# hvreg_feedback_2PS.net
KiCad netlist of a schematic drawn in EAGLE
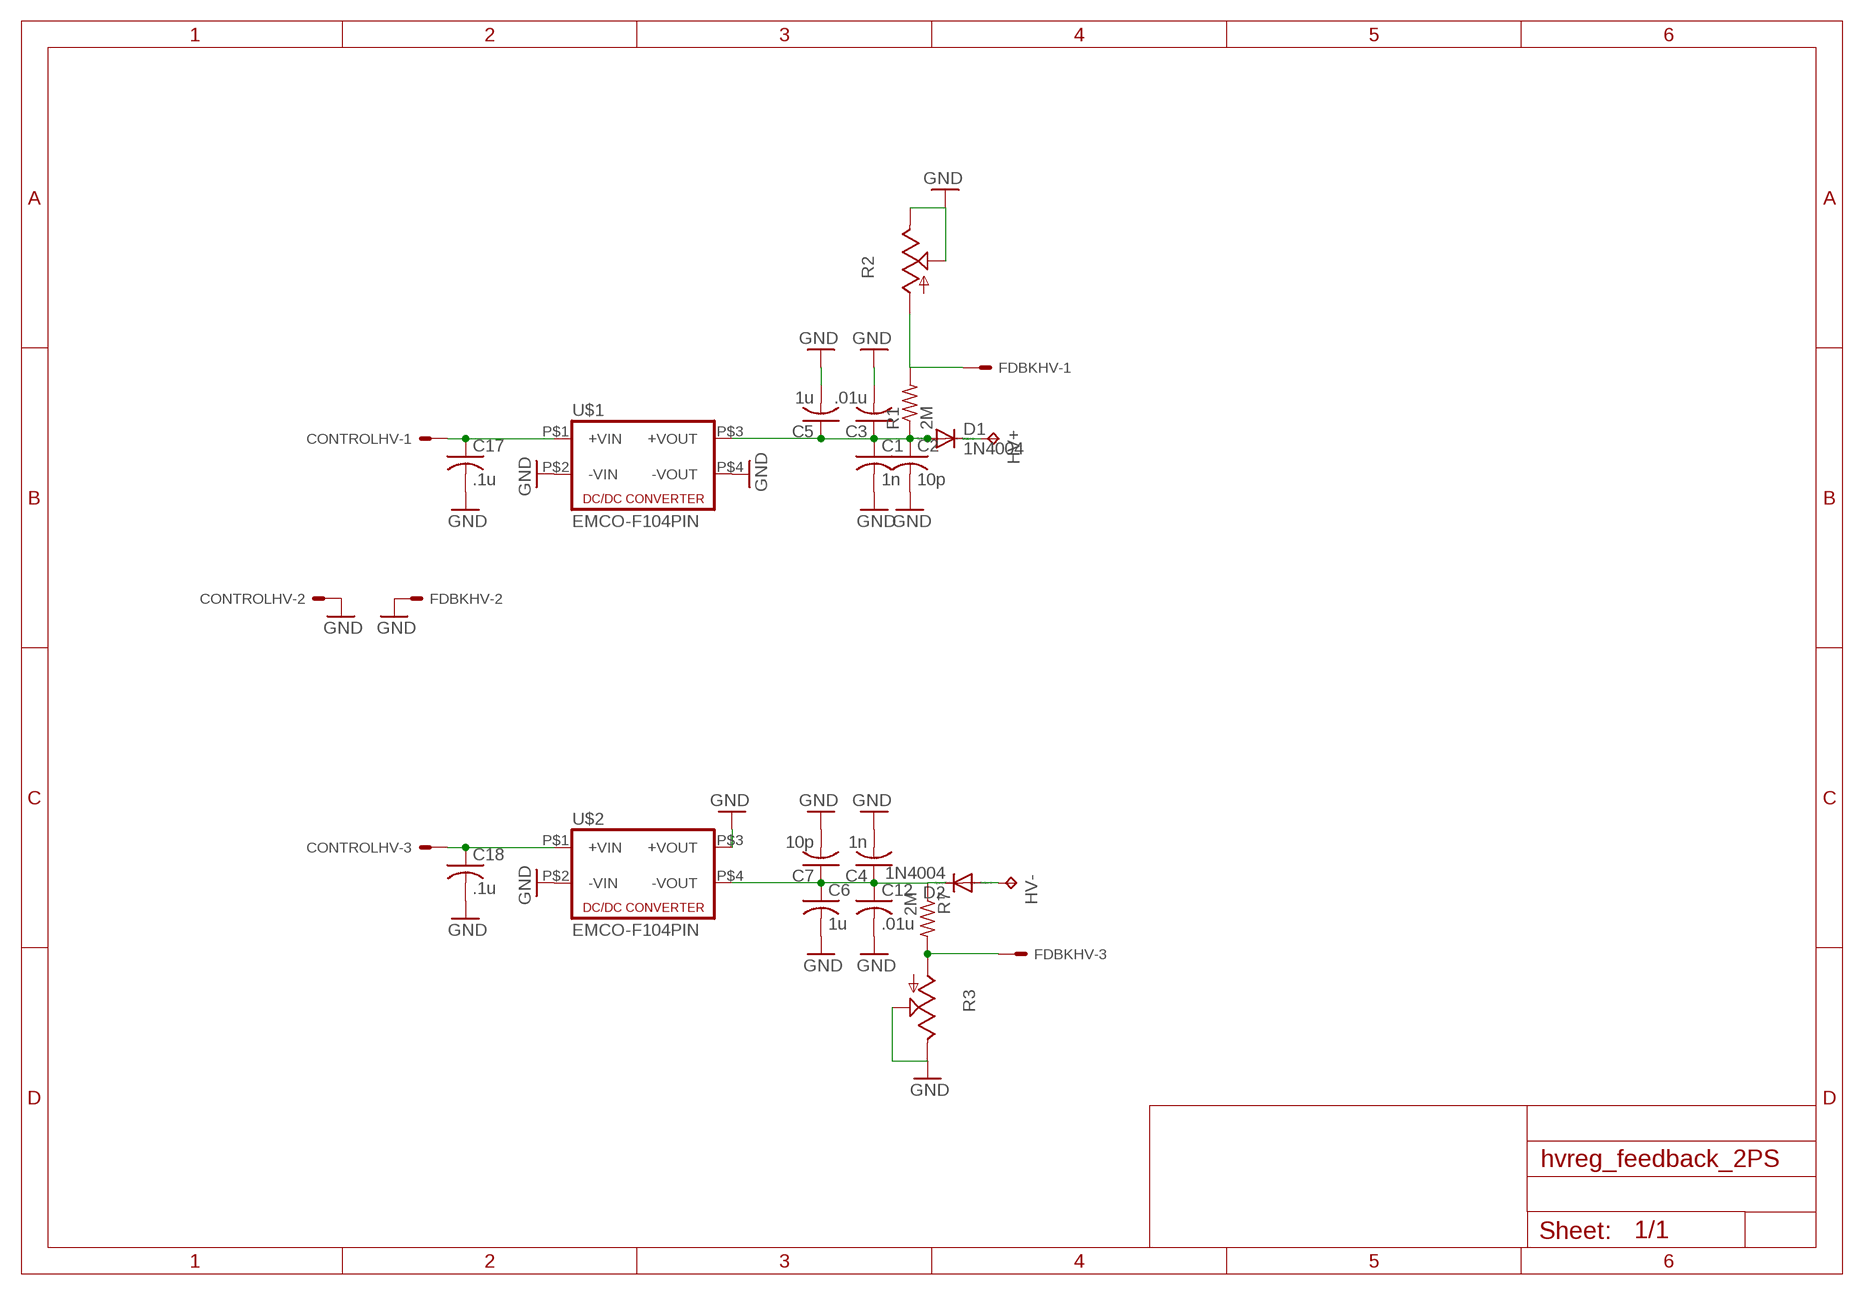
[diagram p0: schematic, sheet 1]

(export (version "E")
  (design (tool "Eeschema 10.0.6"))
  (components
    (comp (ref "C1")
      (value "1n")
      (footprint "eagle-import:C102-043X133")
      (libsource (lib "eagle-import") (part "C-US102-043X133"))
    )
    (comp (ref "C2")
      (value "10p")
      (footprint "eagle-import:C102-043X133")
      (libsource (lib "eagle-import") (part "C-US102-043X133"))
    )
    (comp (ref "C3")
      (value ".01u")
      (footprint "eagle-import:C102-043X133")
      (libsource (lib "eagle-import") (part "C-US102-043X133"))
    )
    (comp (ref "C4")
      (value "1n")
      (footprint "eagle-import:C102-043X133")
      (libsource (lib "eagle-import") (part "C-US102-043X133"))
    )
    (comp (ref "C5")
      (value "1u")
      (footprint "eagle-import:C275-205X316")
      (libsource (lib "eagle-import") (part "C-US275-205X316"))
    )
    (comp (ref "C6")
      (value "1u")
      (footprint "eagle-import:C275-205X316")
      (libsource (lib "eagle-import") (part "C-US275-205X316"))
    )
    (comp (ref "C7")
      (value "10p")
      (footprint "eagle-import:C102-043X133")
      (libsource (lib "eagle-import") (part "C-US102-043X133"))
    )
    (comp (ref "C12")
      (value ".01u")
      (footprint "eagle-import:C102-043X133")
      (libsource (lib "eagle-import") (part "C-US102-043X133"))
    )
    (comp (ref "C17")
      (value ".1u")
      (footprint "eagle-import:C225-113X268")
      (libsource (lib "eagle-import") (part "C-US225-113X268"))
    )
    (comp (ref "C18")
      (value ".1u")
      (footprint "eagle-import:C225-113X268")
      (libsource (lib "eagle-import") (part "C-US225-113X268"))
    )
    (comp (ref "CONTROLHV")
      (value "KK-156-3")
      (footprint "eagle-import:KK-156-3")
      (libsource (lib "eagle-import") (part "KK-156-3"))
    )
    (comp (ref "D1")
      (value "1N4004")
      (footprint "eagle-import:DO41-10")
      (libsource (lib "eagle-import") (part "1N4004"))
    )
    (comp (ref "D2")
      (value "1N4004")
      (footprint "eagle-import:DO41-10")
      (libsource (lib "eagle-import") (part "1N4004"))
    )
    (comp (ref "FDBKHV")
      (value "KK-156-3")
      (footprint "eagle-import:KK-156-3")
      (libsource (lib "eagle-import") (part "KK-156-3"))
    )
    (comp (ref "HV+")
      (value "TPPAD1-20Y")
      (footprint "eagle-import:P1-20Y")
      (libsource (lib "eagle-import") (part "TPPAD1-20Y"))
    )
    (comp (ref "HV-")
      (value "TPPAD1-20Y")
      (footprint "eagle-import:P1-20Y")
      (libsource (lib "eagle-import") (part "TPPAD1-20Y"))
    )
    (comp (ref "R1")
      (value "2M")
      (footprint "eagle-import:P0613_15")
      (libsource (lib "eagle-import") (part "R-US_0613/15"))
    )
    (comp (ref "R2")
      (value "TRIM_US-B90P")
      (footprint "eagle-import:SP19L")
      (libsource (lib "eagle-import") (part "TRIM_US-B90P"))
    )
    (comp (ref "R3")
      (value "TRIM_US-B90P")
      (footprint "eagle-import:SP19L")
      (libsource (lib "eagle-import") (part "TRIM_US-B90P"))
    )
    (comp (ref "R7")
      (value "2M")
      (footprint "eagle-import:P0613_15")
      (libsource (lib "eagle-import") (part "R-US_0613/15"))
    )
    (comp (ref "U$1")
      (value "EMCO-F104PIN")
      (footprint "eagle-import:EMCO-F")
      (libsource (lib "eagle-import") (part "EMCO-F104PIN"))
    )
    (comp (ref "U$2")
      (value "EMCO-F104PIN")
      (footprint "eagle-import:EMCO-F")
      (libsource (lib "eagle-import") (part "EMCO-F104PIN"))
    )
  )
  (nets
    (net (code "1") (name "GND") (class "Default")
      (node (ref "C1") (pin "2") (pinfunction "2_2") (pintype "passive"))
      (node (ref "C12") (pin "2") (pinfunction "2_2") (pintype "passive"))
      (node (ref "C17") (pin "2") (pinfunction "2_2") (pintype "passive"))
      (node (ref "C18") (pin "2") (pinfunction "2_2") (pintype "passive"))
      (node (ref "C2") (pin "2") (pinfunction "2_2") (pintype "passive"))
      (node (ref "C3") (pin "2") (pinfunction "2_2") (pintype "passive"))
      (node (ref "C4") (pin "2") (pinfunction "2_2") (pintype "passive"))
      (node (ref "C5") (pin "2") (pinfunction "2_2") (pintype "passive"))
      (node (ref "C6") (pin "2") (pinfunction "2_2") (pintype "passive"))
      (node (ref "C7") (pin "2") (pinfunction "2_2") (pintype "passive"))
      (node (ref "CONTROLHV") (pin "2") (pinfunction "S_2") (pintype "passive"))
      (node (ref "FDBKHV") (pin "2") (pinfunction "S_2") (pintype "passive"))
      (node (ref "R2") (pin "E") (pinfunction "E_E") (pintype "passive"))
      (node (ref "R2") (pin "S") (pinfunction "S_S") (pintype "passive"))
      (node (ref "R3") (pin "E") (pinfunction "E_E") (pintype "passive"))
      (node (ref "R3") (pin "S") (pinfunction "S_S") (pintype "passive"))
      (node (ref "U$1") (pin "P$2") (pinfunction "-VIN_P$2") (pintype "passive"))
      (node (ref "U$1") (pin "P$4") (pinfunction "-VOUT_P$4") (pintype "passive"))
      (node (ref "U$2") (pin "P$2") (pinfunction "-VIN_P$2") (pintype "passive"))
      (node (ref "U$2") (pin "P$3") (pinfunction "+VOUT_P$3") (pintype "passive"))
    )
    (net (code "2") (name "Net-(CONTROLHVA-S)") (class "Default")
      (node (ref "C17") (pin "1") (pinfunction "1_1") (pintype "passive"))
      (node (ref "CONTROLHV") (pin "1") (pinfunction "S_1") (pintype "passive"))
      (node (ref "U$1") (pin "P$1") (pinfunction "+VIN_P$1") (pintype "passive"))
    )
    (net (code "3") (name "Net-(CONTROLHVC-S)") (class "Default")
      (node (ref "C18") (pin "1") (pinfunction "1_1") (pintype "passive"))
      (node (ref "CONTROLHV") (pin "3") (pinfunction "S_3") (pintype "passive"))
      (node (ref "U$2") (pin "P$1") (pinfunction "+VIN_P$1") (pintype "passive"))
    )
    (net (code "4") (name "Net-(D1-PadC)") (class "Default")
      (node (ref "D1") (pin "C") (pinfunction "C_C") (pintype "passive"))
      (node (ref "HV+") (pin "TP") (pinfunction "TP_TP") (pintype "input"))
    )
    (net (code "5") (name "Net-(D2-PadA)") (class "Default")
      (node (ref "D2") (pin "A") (pinfunction "A_A") (pintype "passive"))
      (node (ref "HV-") (pin "TP") (pinfunction "TP_TP") (pintype "input"))
    )
    (net (code "6") (name "Net-(FDBKHVA-S)") (class "Default")
      (node (ref "FDBKHV") (pin "1") (pinfunction "S_1") (pintype "passive"))
      (node (ref "R1") (pin "2") (pinfunction "2_2") (pintype "passive"))
      (node (ref "R2") (pin "A") (pinfunction "A_A") (pintype "passive"))
    )
    (net (code "7") (name "Net-(FDBKHVC-S)") (class "Default")
      (node (ref "FDBKHV") (pin "3") (pinfunction "S_3") (pintype "passive"))
      (node (ref "R3") (pin "A") (pinfunction "A_A") (pintype "passive"))
      (node (ref "R7") (pin "2") (pinfunction "2_2") (pintype "passive"))
    )
    (net (code "8") (name "Net-(U$1-+VOUT)") (class "Default")
      (node (ref "C1") (pin "1") (pinfunction "1_1") (pintype "passive"))
      (node (ref "C2") (pin "1") (pinfunction "1_1") (pintype "passive"))
      (node (ref "C3") (pin "1") (pinfunction "1_1") (pintype "passive"))
      (node (ref "C5") (pin "1") (pinfunction "1_1") (pintype "passive"))
      (node (ref "D1") (pin "A") (pinfunction "A_A") (pintype "passive"))
      (node (ref "R1") (pin "1") (pinfunction "1_1") (pintype "passive"))
      (node (ref "U$1") (pin "P$3") (pinfunction "+VOUT_P$3") (pintype "passive"))
    )
    (net (code "9") (name "Net-(U$2--VOUT)") (class "Default")
      (node (ref "C12") (pin "1") (pinfunction "1_1") (pintype "passive"))
      (node (ref "C4") (pin "1") (pinfunction "1_1") (pintype "passive"))
      (node (ref "C6") (pin "1") (pinfunction "1_1") (pintype "passive"))
      (node (ref "C7") (pin "1") (pinfunction "1_1") (pintype "passive"))
      (node (ref "D2") (pin "C") (pinfunction "C_C") (pintype "passive"))
      (node (ref "R7") (pin "1") (pinfunction "1_1") (pintype "passive"))
      (node (ref "U$2") (pin "P$4") (pinfunction "-VOUT_P$4") (pintype "passive"))
    )
  )
)
